# receiver_pcb.net
KiCad netlist of a schematic drawn in EAGLE
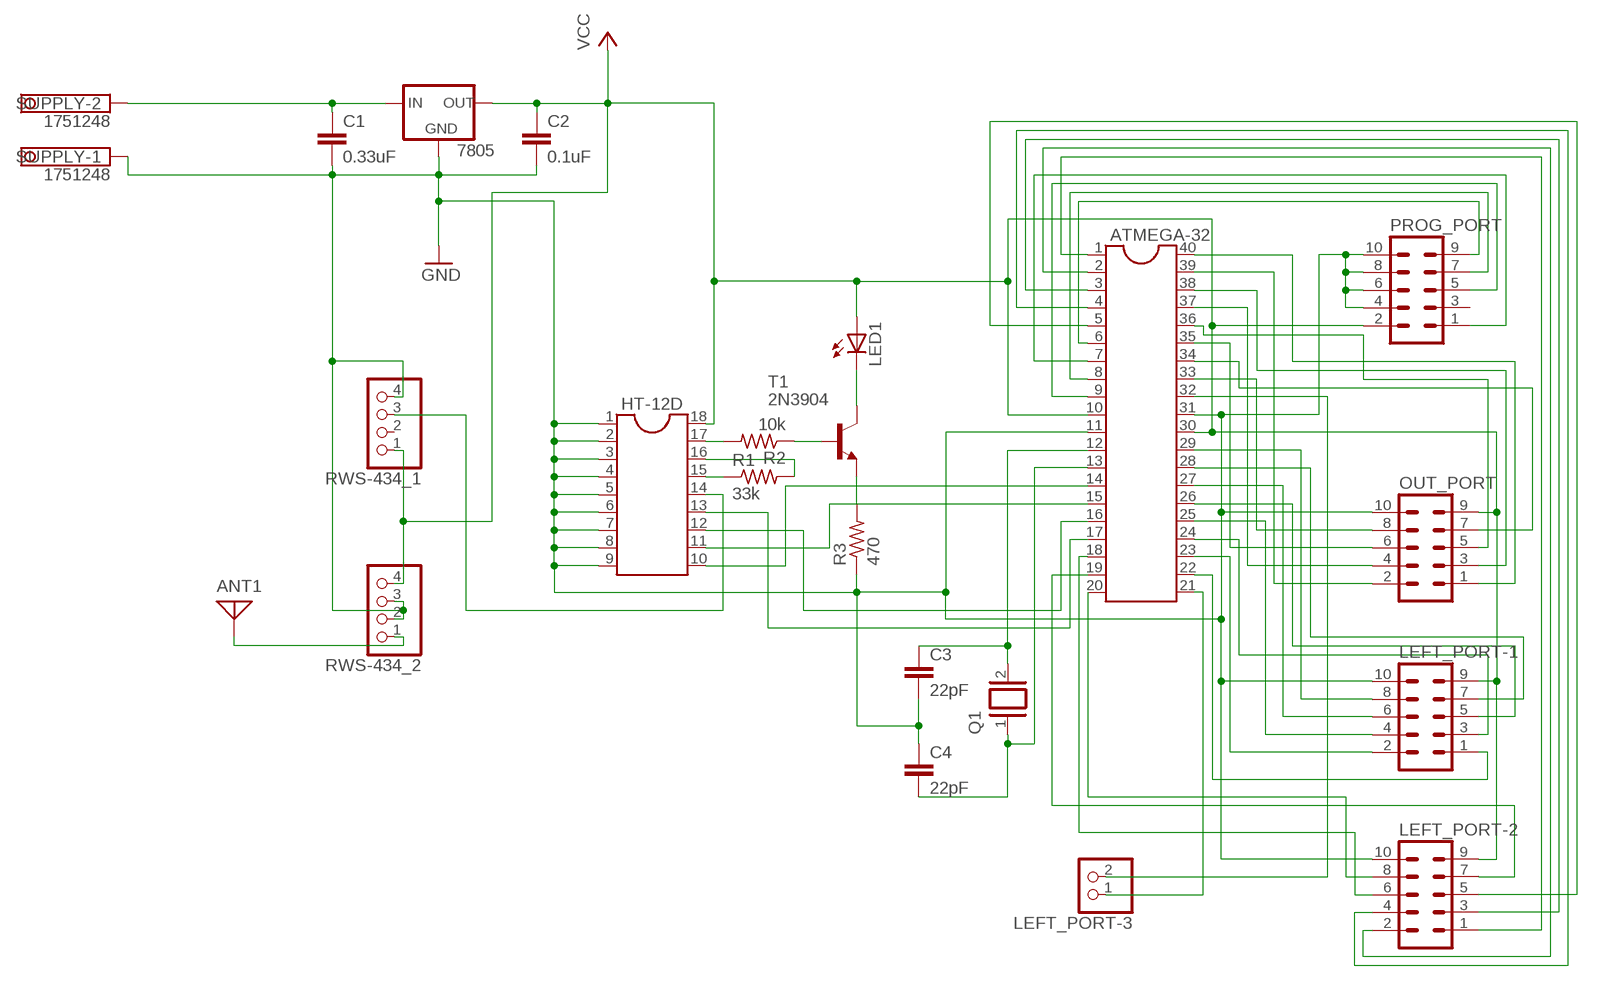
[diagram p0: schematic, sheet 1]

(export (version "E")
  (design (tool "Eeschema 10.0.6"))
  (components
    (comp (ref "7805")
      (value "78XXS")
      (footprint "eagle-import:78XXS")
      (libsource (lib "eagle-import") (part "78XXS"))
    )
    (comp (ref "ANT1")
      (value "ANTENNA")
      (footprint "eagle-import:PAD-01")
      (libsource (lib "eagle-import") (part "ANTENNA"))
    )
    (comp (ref "ATMEGA-32")
      (value "DIL40")
      (footprint "eagle-import:DIL40")
      (libsource (lib "eagle-import") (part "DIL40"))
    )
    (comp (ref "C1")
      (value "0.33uF")
      (footprint "eagle-import:C2.5-2")
      (libsource (lib "eagle-import") (part "C2.5/2"))
    )
    (comp (ref "C2")
      (value "0.1uF")
      (footprint "eagle-import:C2.5-2")
      (libsource (lib "eagle-import") (part "C2.5/2"))
    )
    (comp (ref "C3")
      (value "22pF")
      (footprint "eagle-import:C2.5-2")
      (libsource (lib "eagle-import") (part "C2.5/2"))
    )
    (comp (ref "C4")
      (value "22pF")
      (footprint "eagle-import:C2.5-2")
      (libsource (lib "eagle-import") (part "C2.5/2"))
    )
    (comp (ref "HT-12D")
      (value "DIL18")
      (footprint "eagle-import:DIL18")
      (libsource (lib "eagle-import") (part "DIL18"))
    )
    (comp (ref "LED1")
      (value "LED5MM")
      (footprint "eagle-import:LED5MM")
      (libsource (lib "eagle-import") (part "LED5MM"))
    )
    (comp (ref "LEFT_PORT-1")
      (value "ML10")
      (footprint "eagle-import:ML10")
      (libsource (lib "eagle-import") (part "ML10"))
    )
    (comp (ref "LEFT_PORT-2")
      (value "ML10")
      (footprint "eagle-import:ML10")
      (libsource (lib "eagle-import") (part "ML10"))
    )
    (comp (ref "LEFT_PORT-3")
      (value "PINHD-1X2")
      (footprint "eagle-import:1X02")
      (libsource (lib "eagle-import") (part "PINHD-1X2"))
    )
    (comp (ref "OUT_PORT")
      (value "ML10")
      (footprint "eagle-import:ML10")
      (libsource (lib "eagle-import") (part "ML10"))
    )
    (comp (ref "PROG_PORT")
      (value "ML10")
      (footprint "eagle-import:ML10")
      (libsource (lib "eagle-import") (part "ML10"))
    )
    (comp (ref "Q1")
      (value "XTAL/S")
      (footprint "eagle-import:QS")
      (libsource (lib "eagle-import") (part "XTAL/S"))
    )
    (comp (ref "R1")
      (value "33k")
      (footprint "eagle-import:0204_5")
      (libsource (lib "eagle-import") (part "R-US_0204/5"))
    )
    (comp (ref "R2")
      (value "10k")
      (footprint "eagle-import:0204_5")
      (libsource (lib "eagle-import") (part "R-US_0204/5"))
    )
    (comp (ref "R3")
      (value "470")
      (footprint "eagle-import:0204_5")
      (libsource (lib "eagle-import") (part "R-US_0204/5"))
    )
    (comp (ref "RWS-434_1")
      (value "PINHD-1X4")
      (footprint "eagle-import:1X04")
      (libsource (lib "eagle-import") (part "PINHD-1X4"))
    )
    (comp (ref "RWS-434_2")
      (value "PINHD-1X4")
      (footprint "eagle-import:1X04")
      (libsource (lib "eagle-import") (part "PINHD-1X4"))
    )
    (comp (ref "SUPPLY")
      (value "1751248")
      (footprint "eagle-import:1751248")
      (libsource (lib "eagle-import") (part "1751248"))
    )
    (comp (ref "T1")
      (value "2N3904")
      (footprint "eagle-import:TO92")
      (libsource (lib "eagle-import") (part "2N3904"))
    )
  )
  (nets
    (net (code "1") (name "GND") (class "Default")
      (node (ref "7805") (pin "GND") (pinfunction "GND_GND") (pintype "input"))
      (node (ref "ATMEGA-32") (pin "11") (pinfunction "11_11") (pintype "passive"))
      (node (ref "ATMEGA-32") (pin "31") (pinfunction "31_31") (pintype "passive"))
      (node (ref "C1") (pin "2") (pinfunction "2_2") (pintype "passive"))
      (node (ref "C2") (pin "2") (pinfunction "2_2") (pintype "passive"))
      (node (ref "C3") (pin "2") (pinfunction "2_2") (pintype "passive"))
      (node (ref "C4") (pin "1") (pinfunction "1_1") (pintype "passive"))
      (node (ref "HT-12D") (pin "1") (pinfunction "1_1") (pintype "passive"))
      (node (ref "HT-12D") (pin "2") (pinfunction "2_2") (pintype "passive"))
      (node (ref "HT-12D") (pin "3") (pinfunction "3_3") (pintype "passive"))
      (node (ref "HT-12D") (pin "4") (pinfunction "4_4") (pintype "passive"))
      (node (ref "HT-12D") (pin "5") (pinfunction "5_5") (pintype "passive"))
      (node (ref "HT-12D") (pin "6") (pinfunction "6_6") (pintype "passive"))
      (node (ref "HT-12D") (pin "7") (pinfunction "7_7") (pintype "passive"))
      (node (ref "HT-12D") (pin "8") (pinfunction "8_8") (pintype "passive"))
      (node (ref "HT-12D") (pin "9") (pinfunction "9_9") (pintype "passive"))
      (node (ref "LEFT_PORT-1") (pin "10") (pinfunction "10_10") (pintype "passive"))
      (node (ref "LEFT_PORT-2") (pin "10") (pinfunction "10_10") (pintype "passive"))
      (node (ref "OUT_PORT") (pin "10") (pinfunction "10_10") (pintype "passive"))
      (node (ref "PROG_PORT") (pin "10") (pinfunction "10_10") (pintype "passive"))
      (node (ref "PROG_PORT") (pin "4") (pinfunction "4_4") (pintype "passive"))
      (node (ref "PROG_PORT") (pin "6") (pinfunction "6_6") (pintype "passive"))
      (node (ref "PROG_PORT") (pin "8") (pinfunction "8_8") (pintype "passive"))
      (node (ref "R3") (pin "1") (pinfunction "1_1") (pintype "passive"))
      (node (ref "RWS-434_1") (pin "4") (pinfunction "4_4") (pintype "passive"))
      (node (ref "RWS-434_2") (pin "2") (pinfunction "2_2") (pintype "passive"))
      (node (ref "RWS-434_2") (pin "3") (pinfunction "3_3") (pintype "passive"))
      (node (ref "SUPPLY") (pin "1") (pinfunction "K_1") (pintype "passive"))
    )
    (net (code "2") (name "Net-(ANT1-Pad1)") (class "Default")
      (node (ref "ANT1") (pin "1") (pinfunction "1_1") (pintype "output"))
      (node (ref "RWS-434_2") (pin "1") (pinfunction "1_1") (pintype "passive"))
    )
    (net (code "3") (name "Net-(ATMEGA-32-Pad1)") (class "Default")
      (node (ref "ATMEGA-32") (pin "1") (pinfunction "1_1") (pintype "passive"))
      (node (ref "LEFT_PORT-2") (pin "1") (pinfunction "1_1") (pintype "passive"))
    )
    (net (code "4") (name "Net-(ATMEGA-32-Pad2)") (class "Default")
      (node (ref "ATMEGA-32") (pin "2") (pinfunction "2_2") (pintype "passive"))
      (node (ref "LEFT_PORT-2") (pin "2") (pinfunction "2_2") (pintype "passive"))
    )
    (net (code "5") (name "Net-(ATMEGA-32-Pad3)") (class "Default")
      (node (ref "ATMEGA-32") (pin "3") (pinfunction "3_3") (pintype "passive"))
      (node (ref "LEFT_PORT-2") (pin "3") (pinfunction "3_3") (pintype "passive"))
    )
    (net (code "6") (name "Net-(ATMEGA-32-Pad4)") (class "Default")
      (node (ref "ATMEGA-32") (pin "4") (pinfunction "4_4") (pintype "passive"))
      (node (ref "LEFT_PORT-2") (pin "4") (pinfunction "4_4") (pintype "passive"))
    )
    (net (code "7") (name "Net-(ATMEGA-32-Pad5)") (class "Default")
      (node (ref "ATMEGA-32") (pin "5") (pinfunction "5_5") (pintype "passive"))
      (node (ref "LEFT_PORT-2") (pin "5") (pinfunction "5_5") (pintype "passive"))
    )
    (net (code "8") (name "Net-(ATMEGA-32-Pad6)") (class "Default")
      (node (ref "ATMEGA-32") (pin "6") (pinfunction "6_6") (pintype "passive"))
      (node (ref "PROG_PORT") (pin "9") (pinfunction "9_9") (pintype "passive"))
    )
    (net (code "9") (name "Net-(ATMEGA-32-Pad7)") (class "Default")
      (node (ref "ATMEGA-32") (pin "7") (pinfunction "7_7") (pintype "passive"))
      (node (ref "PROG_PORT") (pin "1") (pinfunction "1_1") (pintype "passive"))
    )
    (net (code "10") (name "Net-(ATMEGA-32-Pad8)") (class "Default")
      (node (ref "ATMEGA-32") (pin "8") (pinfunction "8_8") (pintype "passive"))
      (node (ref "PROG_PORT") (pin "7") (pinfunction "7_7") (pintype "passive"))
    )
    (net (code "11") (name "Net-(ATMEGA-32-Pad9)") (class "Default")
      (node (ref "ATMEGA-32") (pin "9") (pinfunction "9_9") (pintype "passive"))
      (node (ref "PROG_PORT") (pin "5") (pinfunction "5_5") (pintype "passive"))
    )
    (net (code "12") (name "Net-(ATMEGA-32-Pad12)") (class "Default")
      (node (ref "ATMEGA-32") (pin "12") (pinfunction "12_12") (pintype "passive"))
      (node (ref "C3") (pin "1") (pinfunction "1_1") (pintype "passive"))
      (node (ref "Q1") (pin "2") (pinfunction "2_2") (pintype "passive"))
    )
    (net (code "13") (name "Net-(ATMEGA-32-Pad13)") (class "Default")
      (node (ref "ATMEGA-32") (pin "13") (pinfunction "13_13") (pintype "passive"))
      (node (ref "C4") (pin "2") (pinfunction "2_2") (pintype "passive"))
      (node (ref "Q1") (pin "1") (pinfunction "1_1") (pintype "passive"))
    )
    (net (code "14") (name "Net-(ATMEGA-32-Pad14)") (class "Default")
      (node (ref "ATMEGA-32") (pin "14") (pinfunction "14_14") (pintype "passive"))
      (node (ref "HT-12D") (pin "10") (pinfunction "10_10") (pintype "passive"))
    )
    (net (code "15") (name "Net-(ATMEGA-32-Pad15)") (class "Default")
      (node (ref "ATMEGA-32") (pin "15") (pinfunction "15_15") (pintype "passive"))
      (node (ref "HT-12D") (pin "11") (pinfunction "11_11") (pintype "passive"))
    )
    (net (code "16") (name "Net-(ATMEGA-32-Pad16)") (class "Default")
      (node (ref "ATMEGA-32") (pin "16") (pinfunction "16_16") (pintype "passive"))
      (node (ref "HT-12D") (pin "12") (pinfunction "12_12") (pintype "passive"))
    )
    (net (code "17") (name "Net-(ATMEGA-32-Pad17)") (class "Default")
      (node (ref "ATMEGA-32") (pin "17") (pinfunction "17_17") (pintype "passive"))
      (node (ref "HT-12D") (pin "13") (pinfunction "13_13") (pintype "passive"))
    )
    (net (code "18") (name "Net-(ATMEGA-32-Pad18)") (class "Default")
      (node (ref "ATMEGA-32") (pin "18") (pinfunction "18_18") (pintype "passive"))
      (node (ref "LEFT_PORT-2") (pin "6") (pinfunction "6_6") (pintype "passive"))
    )
    (net (code "19") (name "Net-(ATMEGA-32-Pad19)") (class "Default")
      (node (ref "ATMEGA-32") (pin "19") (pinfunction "19_19") (pintype "passive"))
      (node (ref "LEFT_PORT-2") (pin "7") (pinfunction "7_7") (pintype "passive"))
    )
    (net (code "20") (name "Net-(ATMEGA-32-Pad20)") (class "Default")
      (node (ref "ATMEGA-32") (pin "20") (pinfunction "20_20") (pintype "passive"))
      (node (ref "LEFT_PORT-2") (pin "8") (pinfunction "8_8") (pintype "passive"))
    )
    (net (code "21") (name "Net-(ATMEGA-32-Pad21)") (class "Default")
      (node (ref "ATMEGA-32") (pin "21") (pinfunction "21_21") (pintype "passive"))
      (node (ref "LEFT_PORT-3") (pin "1") (pinfunction "1_1") (pintype "passive"))
    )
    (net (code "22") (name "Net-(ATMEGA-32-Pad22)") (class "Default")
      (node (ref "ATMEGA-32") (pin "22") (pinfunction "22_22") (pintype "passive"))
      (node (ref "LEFT_PORT-1") (pin "1") (pinfunction "1_1") (pintype "passive"))
    )
    (net (code "23") (name "Net-(ATMEGA-32-Pad23)") (class "Default")
      (node (ref "ATMEGA-32") (pin "23") (pinfunction "23_23") (pintype "passive"))
      (node (ref "LEFT_PORT-1") (pin "2") (pinfunction "2_2") (pintype "passive"))
    )
    (net (code "24") (name "Net-(ATMEGA-32-Pad24)") (class "Default")
      (node (ref "ATMEGA-32") (pin "24") (pinfunction "24_24") (pintype "passive"))
      (node (ref "LEFT_PORT-1") (pin "3") (pinfunction "3_3") (pintype "passive"))
    )
    (net (code "25") (name "Net-(ATMEGA-32-Pad25)") (class "Default")
      (node (ref "ATMEGA-32") (pin "25") (pinfunction "25_25") (pintype "passive"))
      (node (ref "LEFT_PORT-1") (pin "4") (pinfunction "4_4") (pintype "passive"))
    )
    (net (code "26") (name "Net-(ATMEGA-32-Pad26)") (class "Default")
      (node (ref "ATMEGA-32") (pin "26") (pinfunction "26_26") (pintype "passive"))
      (node (ref "LEFT_PORT-1") (pin "5") (pinfunction "5_5") (pintype "passive"))
    )
    (net (code "27") (name "Net-(ATMEGA-32-Pad27)") (class "Default")
      (node (ref "ATMEGA-32") (pin "27") (pinfunction "27_27") (pintype "passive"))
      (node (ref "LEFT_PORT-1") (pin "6") (pinfunction "6_6") (pintype "passive"))
    )
    (net (code "28") (name "Net-(ATMEGA-32-Pad28)") (class "Default")
      (node (ref "ATMEGA-32") (pin "28") (pinfunction "28_28") (pintype "passive"))
      (node (ref "LEFT_PORT-1") (pin "7") (pinfunction "7_7") (pintype "passive"))
    )
    (net (code "29") (name "Net-(ATMEGA-32-Pad29)") (class "Default")
      (node (ref "ATMEGA-32") (pin "29") (pinfunction "29_29") (pintype "passive"))
      (node (ref "LEFT_PORT-1") (pin "8") (pinfunction "8_8") (pintype "passive"))
    )
    (net (code "30") (name "Net-(ATMEGA-32-Pad32)") (class "Default")
      (node (ref "ATMEGA-32") (pin "32") (pinfunction "32_32") (pintype "passive"))
      (node (ref "LEFT_PORT-3") (pin "2") (pinfunction "2_2") (pintype "passive"))
    )
    (net (code "31") (name "Net-(ATMEGA-32-Pad33)") (class "Default")
      (node (ref "ATMEGA-32") (pin "33") (pinfunction "33_33") (pintype "passive"))
      (node (ref "OUT_PORT") (pin "8") (pinfunction "8_8") (pintype "passive"))
    )
    (net (code "32") (name "Net-(ATMEGA-32-Pad34)") (class "Default")
      (node (ref "ATMEGA-32") (pin "34") (pinfunction "34_34") (pintype "passive"))
      (node (ref "OUT_PORT") (pin "7") (pinfunction "7_7") (pintype "passive"))
    )
    (net (code "33") (name "Net-(ATMEGA-32-Pad35)") (class "Default")
      (node (ref "ATMEGA-32") (pin "35") (pinfunction "35_35") (pintype "passive"))
      (node (ref "OUT_PORT") (pin "6") (pinfunction "6_6") (pintype "passive"))
    )
    (net (code "34") (name "Net-(ATMEGA-32-Pad36)") (class "Default")
      (node (ref "ATMEGA-32") (pin "36") (pinfunction "36_36") (pintype "passive"))
      (node (ref "OUT_PORT") (pin "5") (pinfunction "5_5") (pintype "passive"))
    )
    (net (code "35") (name "Net-(ATMEGA-32-Pad37)") (class "Default")
      (node (ref "ATMEGA-32") (pin "37") (pinfunction "37_37") (pintype "passive"))
      (node (ref "OUT_PORT") (pin "4") (pinfunction "4_4") (pintype "passive"))
    )
    (net (code "36") (name "Net-(ATMEGA-32-Pad38)") (class "Default")
      (node (ref "ATMEGA-32") (pin "38") (pinfunction "38_38") (pintype "passive"))
      (node (ref "OUT_PORT") (pin "3") (pinfunction "3_3") (pintype "passive"))
    )
    (net (code "37") (name "Net-(ATMEGA-32-Pad39)") (class "Default")
      (node (ref "ATMEGA-32") (pin "39") (pinfunction "39_39") (pintype "passive"))
      (node (ref "OUT_PORT") (pin "2") (pinfunction "2_2") (pintype "passive"))
    )
    (net (code "38") (name "Net-(ATMEGA-32-Pad40)") (class "Default")
      (node (ref "ATMEGA-32") (pin "40") (pinfunction "40_40") (pintype "passive"))
      (node (ref "OUT_PORT") (pin "1") (pinfunction "1_1") (pintype "passive"))
    )
    (net (code "39") (name "Net-(HT-12D-Pad14)") (class "Default")
      (node (ref "HT-12D") (pin "14") (pinfunction "14_14") (pintype "passive"))
      (node (ref "RWS-434_1") (pin "3") (pinfunction "3_3") (pintype "passive"))
    )
    (net (code "40") (name "Net-(HT-12D-Pad15)") (class "Default")
      (node (ref "HT-12D") (pin "15") (pinfunction "15_15") (pintype "passive"))
      (node (ref "R1") (pin "1") (pinfunction "1_1") (pintype "passive"))
    )
    (net (code "41") (name "Net-(HT-12D-Pad16)") (class "Default")
      (node (ref "HT-12D") (pin "16") (pinfunction "16_16") (pintype "passive"))
      (node (ref "R1") (pin "2") (pinfunction "2_2") (pintype "passive"))
    )
    (net (code "42") (name "Net-(HT-12D-Pad17)") (class "Default")
      (node (ref "HT-12D") (pin "17") (pinfunction "17_17") (pintype "passive"))
      (node (ref "R2") (pin "2") (pinfunction "2_2") (pintype "passive"))
    )
    (net (code "43") (name "Net-(LED1-C)") (class "Default")
      (node (ref "LED1") (pin "K") (pinfunction "C_K") (pintype "passive"))
      (node (ref "T1") (pin "1") (pinfunction "C_1") (pintype "passive"))
    )
    (net (code "44") (name "Net-(SUPPLYB-K)") (class "Default")
      (node (ref "7805") (pin "IN") (pinfunction "IN_IN") (pintype "input"))
      (node (ref "C1") (pin "1") (pinfunction "1_1") (pintype "passive"))
      (node (ref "SUPPLY") (pin "2") (pinfunction "K_2") (pintype "passive"))
    )
    (net (code "45") (name "Net-(T1-B)") (class "Default")
      (node (ref "R2") (pin "1") (pinfunction "1_1") (pintype "passive"))
      (node (ref "T1") (pin "2") (pinfunction "B_2") (pintype "passive"))
    )
    (net (code "46") (name "Net-(T1-E)") (class "Default")
      (node (ref "R3") (pin "2") (pinfunction "2_2") (pintype "passive"))
      (node (ref "T1") (pin "3") (pinfunction "E_3") (pintype "passive"))
    )
    (net (code "47") (name "VCC") (class "Default")
      (node (ref "7805") (pin "OUT") (pinfunction "OUT_OUT") (pintype "passive"))
      (node (ref "ATMEGA-32") (pin "10") (pinfunction "10_10") (pintype "passive"))
      (node (ref "ATMEGA-32") (pin "30") (pinfunction "30_30") (pintype "passive"))
      (node (ref "C2") (pin "1") (pinfunction "1_1") (pintype "passive"))
      (node (ref "HT-12D") (pin "18") (pinfunction "18_18") (pintype "passive"))
      (node (ref "LED1") (pin "A") (pinfunction "A_A") (pintype "passive"))
      (node (ref "LEFT_PORT-1") (pin "9") (pinfunction "9_9") (pintype "passive"))
      (node (ref "LEFT_PORT-2") (pin "9") (pinfunction "9_9") (pintype "passive"))
      (node (ref "OUT_PORT") (pin "9") (pinfunction "9_9") (pintype "passive"))
      (node (ref "PROG_PORT") (pin "2") (pinfunction "2_2") (pintype "passive"))
      (node (ref "RWS-434_1") (pin "1") (pinfunction "1_1") (pintype "passive"))
      (node (ref "RWS-434_2") (pin "4") (pinfunction "4_4") (pintype "passive"))
    )
    (net (code "48") (name "unconnected-(PROG_PORT-Pad3)") (class "Default")
      (node (ref "PROG_PORT") (pin "3") (pinfunction "3_3") (pintype "passive"))
    )
    (net (code "49") (name "unconnected-(RWS-434_1-Pad2)") (class "Default")
      (node (ref "RWS-434_1") (pin "2") (pinfunction "2_2") (pintype "passive"))
    )
  )
)
